# STEERING_WHEEL_SWITCHES.net
KiCad netlist of a schematic drawn in Altium Designer
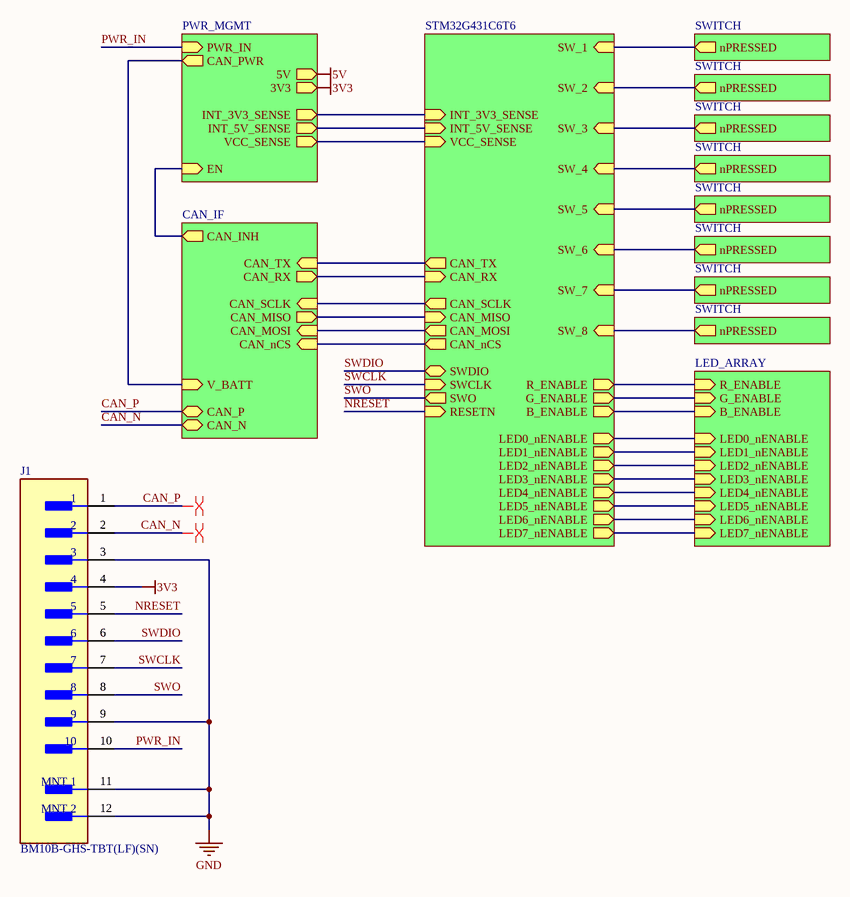
[diagram p0: STEERING_WHEEL_SWITCHES.SchDoc]

(export (version "E")
  (design (tool "Eeschema 10.0.6"))
  (components
    (comp (ref "J1")
      (value "BM10B-GHS-TBT(LF)(SN)")
      (footprint "FP-BM10B-GHS-TBT_LF_SN-MFG")
      (description "Connector Header Surface Mount 10 position 0.049\" (1.25mm)")
      (libsource (lib "Altium Content Vault") (part "e2e6c716b162496128e6422c56d8ed8"))
    )
  )
  (nets
    (net (code "5") (name "/CAN_N") (class "Default")
      (node (ref "J1") (pin "2") (pinfunction "2_2") (pintype "passive"))
    )
    (net (code "6") (name "/CAN_P") (class "Default")
      (node (ref "J1") (pin "1") (pinfunction "1_1") (pintype "passive"))
    )
    (net (code "23") (name "/NRESET") (class "Default")
      (node (ref "J1") (pin "5") (pinfunction "5_5") (pintype "passive"))
    )
    (net (code "24") (name "/PWR_IN") (class "Default")
      (node (ref "J1") (pin "10") (pinfunction "10_10") (pintype "passive"))
    )
    (net (code "26") (name "/SWCLK") (class "Default")
      (node (ref "J1") (pin "7") (pinfunction "7_7") (pintype "passive"))
    )
    (net (code "27") (name "/SWDIO") (class "Default")
      (node (ref "J1") (pin "6") (pinfunction "6_6") (pintype "passive"))
    )
    (net (code "28") (name "/SWO") (class "Default")
      (node (ref "J1") (pin "8") (pinfunction "8_8") (pintype "passive"))
    )
    (net (code "38") (name "3V3") (class "Default")
      (node (ref "J1") (pin "4") (pinfunction "4_4") (pintype "passive"))
    )
    (net (code "40") (name "GND") (class "Default")
      (node (ref "J1") (pin "11") (pinfunction "MNT_1_11") (pintype "passive"))
      (node (ref "J1") (pin "12") (pinfunction "MNT_2_12") (pintype "passive"))
      (node (ref "J1") (pin "3") (pinfunction "3_3") (pintype "passive"))
      (node (ref "J1") (pin "9") (pinfunction "9_9") (pintype "passive"))
    )
  )
)
